# LED.net
KiCad netlist of a schematic drawn in Altium Designer
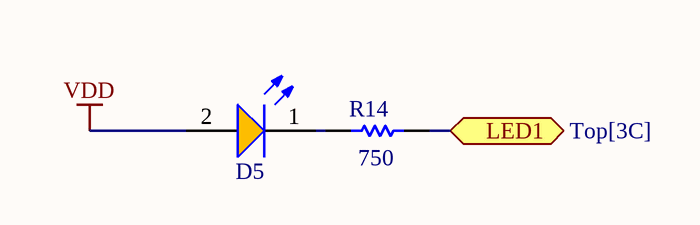
[diagram p0: LED.SchDoc]

(export (version "E")
  (design (tool "Eeschema 10.0.6"))
  (components
    (comp (ref "D5")
      (value "Amber, 2V, 120°")
      (footprint "WL-SMTW_3528")
      (description "WL-SMTW Mono-color TOP LED Waterclear, size 3528, Amber, 2V, 120°")
      (fields
        (field (name "MANUFACTURER PART NUMBER") "150141AS73100")
        (field (name "MANUFACTURER") "Wurth Elektronik")
      )
      (libsource (lib "STEVAL-ESLBLECB") (part "150141AS73100"))
    )
    (comp (ref "R14")
      (value "750")
      (footprint "R0402")
      (description "SMD Chip Resistor, 750 Ohm")
      (fields (field (name "MANUFACTURER") "Wurth") (field (name "MANUFACTURER PART NUMBER") "560112110262"))
      (libsource (lib "MCD_PARTS_database") (part "Resistor"))
    )
  )
  (nets
    (net (code "1") (name "/LED1") (class "Default")
      (node (ref "R14") (pin "2") (pinfunction "2_2") (pintype "passive"))
    )
    (net (code "2") (name "Net-(D5-K)") (class "Default")
      (node (ref "D5") (pin "1") (pinfunction "K_1") (pintype "passive"))
      (node (ref "R14") (pin "1") (pinfunction "1_1") (pintype "passive"))
    )
    (net (code "3") (name "VDD") (class "Default")
      (node (ref "D5") (pin "2") (pinfunction "A_2") (pintype "passive"))
    )
  )
)
